# Sheet1.net
KiCad netlist of a schematic drawn in Altium Designer
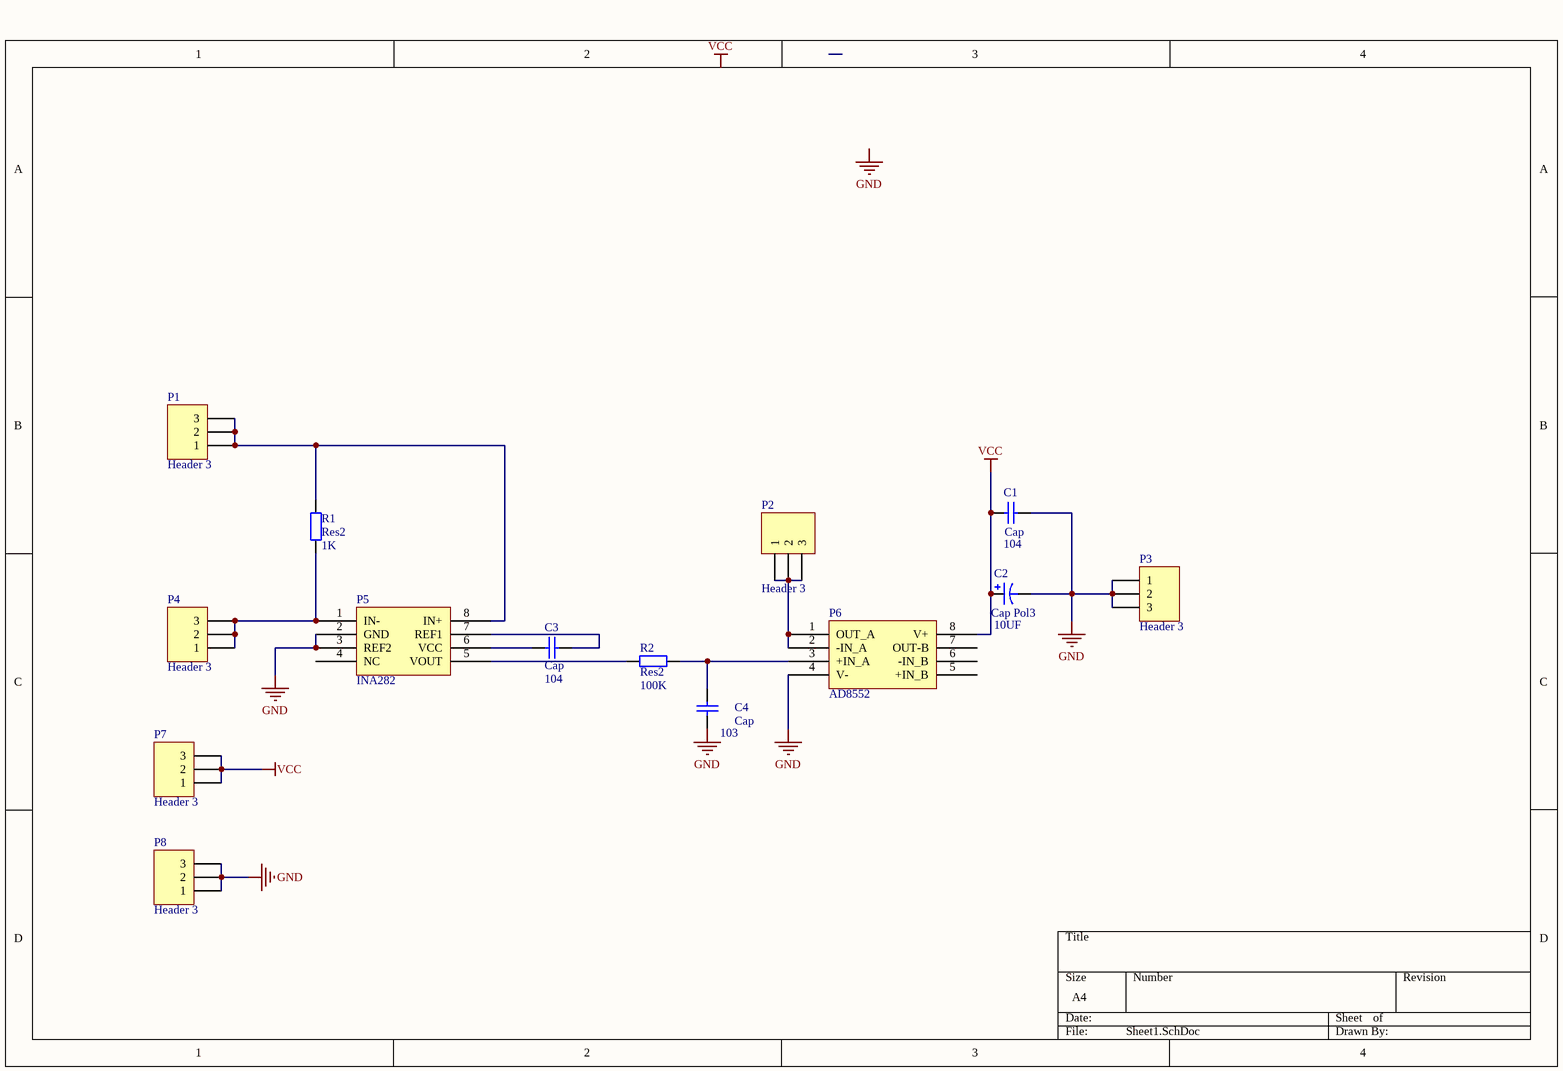
[diagram p0: Sheet1.SchDoc]

(export (version "E")
  (design (tool "Eeschema 10.0.6"))
  (components
    (comp (ref "C1")
      (value "Cap")
      (footprint "BAT-2")
      (description "Capacitor")
      (fields (field (name "ALTIUM_VALUE") "104") (field (name "PUBLISHER") "Altium Limited"))
      (libsource (lib "Miscellaneous Devices") (part "Cap"))
    )
    (comp (ref "C2")
      (value "Cap Pol3")
      (footprint "BAT-2")
      (description "Polarized Capacitor (Surface Mount)")
      (fields (field (name "ALTIUM_VALUE") "10UF") (field (name "PUBLISHER") "Altium Limited"))
      (libsource (lib "Miscellaneous Devices") (part "Cap Pol3"))
    )
    (comp (ref "C3")
      (value "Cap")
      (footprint "BAT-2")
      (description "Capacitor")
      (fields (field (name "ALTIUM_VALUE") "104") (field (name "PUBLISHER") "Altium Limited"))
      (libsource (lib "Miscellaneous Devices") (part "Cap"))
    )
    (comp (ref "C4")
      (value "Cap")
      (footprint "BAT-2")
      (description "Capacitor")
      (fields (field (name "ALTIUM_VALUE") "103") (field (name "PUBLISHER") "Altium Limited"))
      (libsource (lib "Miscellaneous Devices") (part "Cap"))
    )
    (comp (ref "P1")
      (value "Header 3")
      (footprint "HDR1X3")
      (description "Header, 3-Pin")
      (fields (field (name "PUBLISHER") "Altium Limited"))
      (libsource (lib "Miscellaneous Connectors") (part "Header 3"))
    )
    (comp (ref "P2")
      (value "Header 3")
      (footprint "HDR1X3")
      (description "Header, 3-Pin")
      (fields (field (name "PUBLISHER") "Altium Limited"))
      (libsource (lib "") (part "Header 3_2"))
    )
    (comp (ref "P3")
      (value "Header 3")
      (footprint "HDR1X3")
      (description "Header, 3-Pin")
      (fields (field (name "PUBLISHER") "Altium Limited"))
      (libsource (lib "") (part "Header 3_1"))
    )
    (comp (ref "P4")
      (value "Header 3")
      (footprint "HDR1X3")
      (description "Header, 3-Pin")
      (fields (field (name "PUBLISHER") "Altium Limited"))
      (libsource (lib "Miscellaneous Connectors") (part "Header 3"))
    )
    (comp (ref "P5") (value "INA282") (footprint "DIP-8") (libsource (lib "Schlib1") (part "INA282")))
    (comp (ref "P6") (value "AD8552") (footprint "DIP-8") (libsource (lib "Schlib1") (part "AD8552")))
    (comp (ref "P7")
      (value "Header 3")
      (footprint "HDR1X3")
      (description "Header, 3-Pin")
      (fields (field (name "PUBLISHER") "Altium Limited"))
      (libsource (lib "Miscellaneous Connectors") (part "Header 3"))
    )
    (comp (ref "P8")
      (value "Header 3")
      (footprint "HDR1X3")
      (description "Header, 3-Pin")
      (fields (field (name "PUBLISHER") "Altium Limited"))
      (libsource (lib "Miscellaneous Connectors") (part "Header 3"))
    )
    (comp (ref "R1")
      (value "Res2")
      (footprint "C")
      (description "Resistor")
      (fields (field (name "ALTIUM_VALUE") "1K") (field (name "PUBLISHER") "Altium Limited"))
      (libsource (lib "Miscellaneous Devices") (part "Res2"))
    )
    (comp (ref "R2")
      (value "Res2")
      (footprint "AXIAL-0.4")
      (description "Resistor")
      (fields (field (name "ALTIUM_VALUE") "100K") (field (name "PUBLISHER") "Altium Limited"))
      (libsource (lib "") (part "Res2_1"))
    )
  )
  (nets
    (net (code "2") (name "GND") (class "Default")
      (node (ref "C1") (pin "2") (pinfunction "2_2") (pintype "passive"))
      (node (ref "C2") (pin "2") (pinfunction "2_2") (pintype "passive"))
      (node (ref "C4") (pin "2") (pinfunction "2_2") (pintype "passive"))
      (node (ref "P3") (pin "1") (pinfunction "1_1") (pintype "passive"))
      (node (ref "P3") (pin "2") (pinfunction "2_2") (pintype "passive"))
      (node (ref "P3") (pin "3") (pinfunction "3_3") (pintype "passive"))
      (node (ref "P5") (pin "2") (pinfunction "GND_2") (pintype "passive"))
      (node (ref "P5") (pin "3") (pinfunction "REF2_3") (pintype "passive"))
      (node (ref "P6") (pin "4") (pinfunction "V-_4") (pintype "passive"))
      (node (ref "P8") (pin "1") (pinfunction "1_1") (pintype "passive"))
      (node (ref "P8") (pin "2") (pinfunction "2_2") (pintype "passive"))
      (node (ref "P8") (pin "3") (pinfunction "3_3") (pintype "passive"))
    )
    (net (code "3") (name "Net-(P5-IN+)") (class "Default")
      (node (ref "P1") (pin "1") (pinfunction "1_1") (pintype "passive"))
      (node (ref "P1") (pin "2") (pinfunction "2_2") (pintype "passive"))
      (node (ref "P1") (pin "3") (pinfunction "3_3") (pintype "passive"))
      (node (ref "P5") (pin "8") (pinfunction "IN+_8") (pintype "passive"))
      (node (ref "R1") (pin "2") (pinfunction "2_2") (pintype "passive"))
    )
    (net (code "4") (name "Net-(P5-IN-)") (class "Default")
      (node (ref "P4") (pin "1") (pinfunction "1_1") (pintype "passive"))
      (node (ref "P4") (pin "2") (pinfunction "2_2") (pintype "passive"))
      (node (ref "P4") (pin "3") (pinfunction "3_3") (pintype "passive"))
      (node (ref "P5") (pin "1") (pinfunction "IN-_1") (pintype "passive"))
      (node (ref "R1") (pin "1") (pinfunction "1_1") (pintype "passive"))
    )
    (net (code "5") (name "Net-(P5-REF1)") (class "Default")
      (node (ref "C3") (pin "2") (pinfunction "2_2") (pintype "passive"))
      (node (ref "P5") (pin "7") (pinfunction "REF1_7") (pintype "passive"))
    )
    (net (code "6") (name "Net-(P5-VCC)") (class "Default")
      (node (ref "C3") (pin "1") (pinfunction "1_1") (pintype "passive"))
      (node (ref "P5") (pin "6") (pinfunction "VCC_6") (pintype "passive"))
    )
    (net (code "7") (name "Net-(P5-VOUT)") (class "Default")
      (node (ref "P5") (pin "5") (pinfunction "VOUT_5") (pintype "passive"))
      (node (ref "R2") (pin "1") (pinfunction "1_1") (pintype "passive"))
    )
    (net (code "8") (name "Net-(P6-+IN_A)") (class "Default")
      (node (ref "C4") (pin "1") (pinfunction "1_1") (pintype "passive"))
      (node (ref "P6") (pin "3") (pinfunction "+IN_A_3") (pintype "passive"))
      (node (ref "R2") (pin "2") (pinfunction "2_2") (pintype "passive"))
    )
    (net (code "9") (name "Net-(P6--IN_A)") (class "Default")
      (node (ref "P2") (pin "1") (pinfunction "1_1") (pintype "passive"))
      (node (ref "P2") (pin "2") (pinfunction "2_2") (pintype "passive"))
      (node (ref "P2") (pin "3") (pinfunction "3_3") (pintype "passive"))
      (node (ref "P6") (pin "1") (pinfunction "OUT_A_1") (pintype "passive"))
      (node (ref "P6") (pin "2") (pinfunction "-IN_A_2") (pintype "passive"))
    )
    (net (code "10") (name "VCC") (class "Default")
      (node (ref "C1") (pin "1") (pinfunction "1_1") (pintype "passive"))
      (node (ref "C2") (pin "1") (pinfunction "1_1") (pintype "passive"))
      (node (ref "P6") (pin "8") (pinfunction "V+_8") (pintype "passive"))
      (node (ref "P7") (pin "1") (pinfunction "1_1") (pintype "passive"))
      (node (ref "P7") (pin "2") (pinfunction "2_2") (pintype "passive"))
      (node (ref "P7") (pin "3") (pinfunction "3_3") (pintype "passive"))
    )
    (net (code "11") (name "unconnected-(P5-NC-Pad4)") (class "Default")
      (node (ref "P5") (pin "4") (pinfunction "NC_4") (pintype "passive"))
    )
    (net (code "12") (name "unconnected-(P6-+IN_B-Pad5)") (class "Default")
      (node (ref "P6") (pin "5") (pinfunction "+IN_B_5") (pintype "passive"))
    )
    (net (code "13") (name "unconnected-(P6--IN_B-Pad6)") (class "Default")
      (node (ref "P6") (pin "6") (pinfunction "-IN_B_6") (pintype "passive"))
    )
    (net (code "14") (name "unconnected-(P6-OUT-B-Pad7)") (class "Default")
      (node (ref "P6") (pin "7") (pinfunction "OUT-B_7") (pintype "passive"))
    )
  )
)
